# FPGA_Inputs.net
KiCad netlist of a schematic drawn in Altium Designer
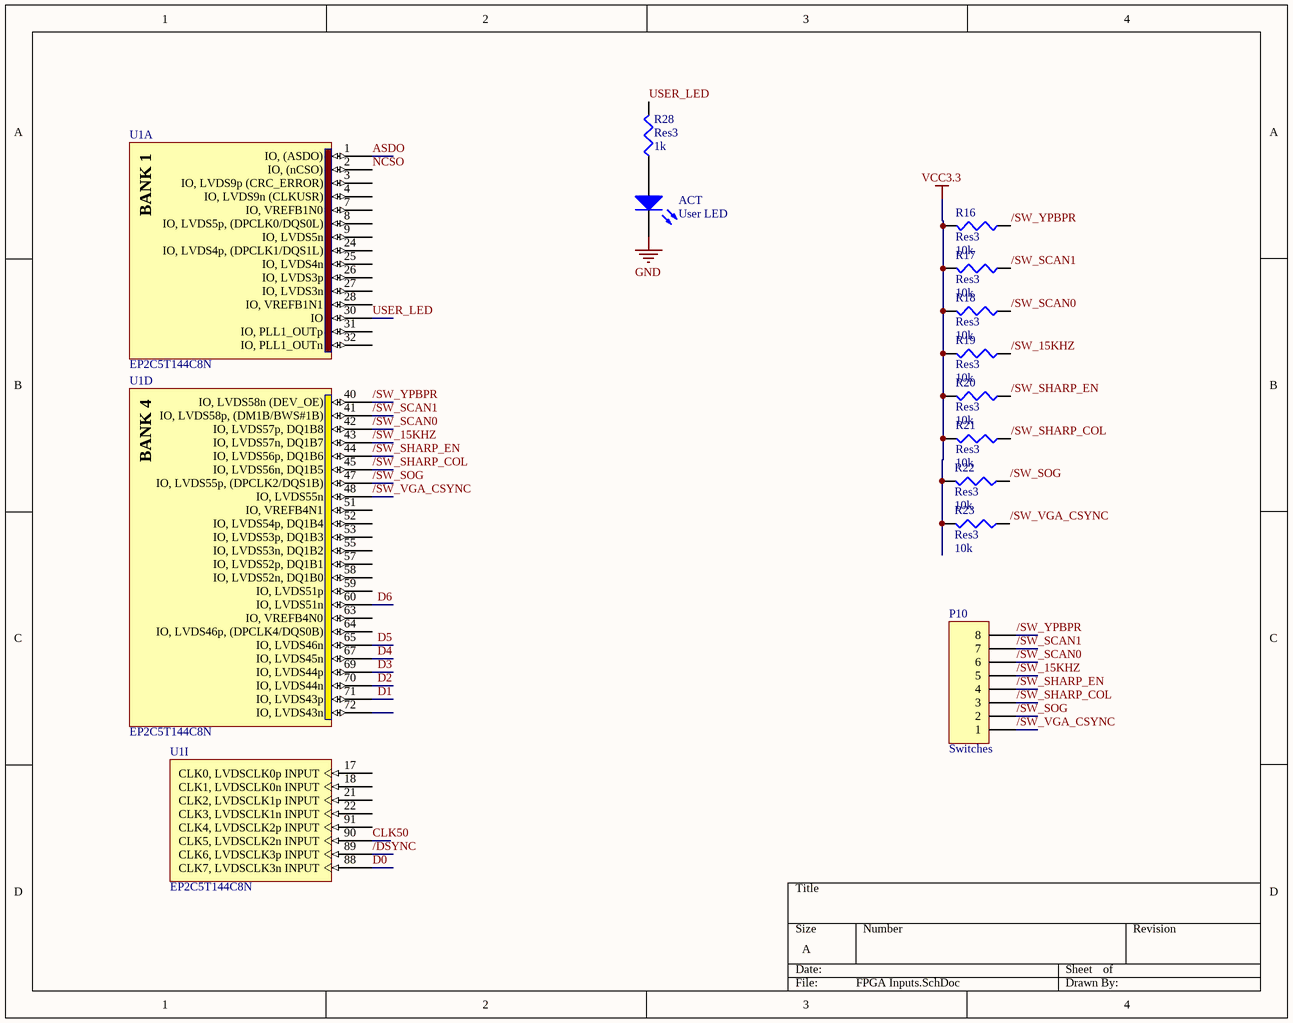
[diagram p0: FPGA Inputs.SchDoc]

(export (version "E")
  (design (tool "Eeschema 10.0.6"))
  (components
    (comp (ref "ACT")
      (value "User LED")
      (footprint "1608[0603]")
      (description "Typical RED, GREEN, YELLOW, AMBER GaAs LED")
      (fields (field (name "PUBLISHER") "Altium Limited"))
      (libsource (lib "Miscellaneous Devices") (part "LED2"))
    )
    (comp (ref "P10")
      (value "Switches")
      (footprint "HDR1X8")
      (description "Header, 8-Pin")
      (fields (field (name "PUBLISHER") "Altium Limited"))
      (libsource (lib "Miscellaneous Connectors") (part "Header 8"))
    )
    (comp (ref "R16")
      (value "Res3")
      (footprint "J1-0603")
      (description "Resistor")
      (fields (field (name "ALTIUM_VALUE") "10k") (field (name "PUBLISHER") "Altium Limited"))
      (libsource (lib "Miscellaneous Devices") (part "Res3"))
    )
    (comp (ref "R17")
      (value "Res3")
      (footprint "J1-0603")
      (description "Resistor")
      (fields (field (name "ALTIUM_VALUE") "10k") (field (name "PUBLISHER") "Altium Limited"))
      (libsource (lib "Miscellaneous Devices") (part "Res3"))
    )
    (comp (ref "R18")
      (value "Res3")
      (footprint "J1-0603")
      (description "Resistor")
      (fields (field (name "ALTIUM_VALUE") "10k") (field (name "PUBLISHER") "Altium Limited"))
      (libsource (lib "Miscellaneous Devices") (part "Res3"))
    )
    (comp (ref "R19")
      (value "Res3")
      (footprint "J1-0603")
      (description "Resistor")
      (fields (field (name "ALTIUM_VALUE") "10k") (field (name "PUBLISHER") "Altium Limited"))
      (libsource (lib "Miscellaneous Devices") (part "Res3"))
    )
    (comp (ref "R20")
      (value "Res3")
      (footprint "J1-0603")
      (description "Resistor")
      (fields (field (name "ALTIUM_VALUE") "10k") (field (name "PUBLISHER") "Altium Limited"))
      (libsource (lib "Miscellaneous Devices") (part "Res3"))
    )
    (comp (ref "R21")
      (value "Res3")
      (footprint "J1-0603")
      (description "Resistor")
      (fields (field (name "ALTIUM_VALUE") "10k") (field (name "PUBLISHER") "Altium Limited"))
      (libsource (lib "Miscellaneous Devices") (part "Res3"))
    )
    (comp (ref "R22")
      (value "Res3")
      (footprint "J1-0603")
      (description "Resistor")
      (fields (field (name "ALTIUM_VALUE") "10k") (field (name "PUBLISHER") "Altium Limited"))
      (libsource (lib "Miscellaneous Devices") (part "Res3"))
    )
    (comp (ref "R23")
      (value "Res3")
      (footprint "J1-0603")
      (description "Resistor")
      (fields (field (name "ALTIUM_VALUE") "10k") (field (name "PUBLISHER") "Altium Limited"))
      (libsource (lib "Miscellaneous Devices") (part "Res3"))
    )
    (comp (ref "R28")
      (value "Res3")
      (footprint "J1-0603")
      (description "Resistor")
      (fields (field (name "ALTIUM_VALUE") "1k") (field (name "PUBLISHER") "Altium Limited"))
      (libsource (lib "Miscellaneous Devices") (part "Res3"))
    )
    (comp (ref "U1")
      (value "EP2C5T144C8N")
      (footprint "TQFP144_N")
      (fields (field (name "PUBLISHER") "Altium Limited"))
      (libsource (lib "Altera Cyclone II") (part "EP2C5T144C8N"))
    )
  )
  (nets
    (net (code "1") (name "/ASDO") (class "Default")
      (node (ref "U1") (pin "1") (pinfunction "IO,_(ASDO)_1") (pintype "bidirectional"))
    )
    (net (code "2") (name "/CLK50") (class "Default")
      (node (ref "U1") (pin "90") (pinfunction "CLK5,_LVDSCLK2n_INPUT_90") (pintype "input"))
    )
    (net (code "3") (name "/D0") (class "Default")
      (node (ref "U1") (pin "88") (pinfunction "CLK7,_LVDSCLK3n_INPUT_88") (pintype "input"))
    )
    (net (code "4") (name "/D1") (class "Default")
      (node (ref "U1") (pin "71") (pinfunction "IO,_LVDS43p_71") (pintype "bidirectional"))
    )
    (net (code "5") (name "/D2") (class "Default")
      (node (ref "U1") (pin "70") (pinfunction "IO,_LVDS44n_70") (pintype "bidirectional"))
    )
    (net (code "6") (name "/D3") (class "Default")
      (node (ref "U1") (pin "69") (pinfunction "IO,_LVDS44p_69") (pintype "bidirectional"))
    )
    (net (code "7") (name "/D4") (class "Default")
      (node (ref "U1") (pin "67") (pinfunction "IO,_LVDS45n_67") (pintype "bidirectional"))
    )
    (net (code "8") (name "/D5") (class "Default")
      (node (ref "U1") (pin "65") (pinfunction "IO,_LVDS46n_65") (pintype "bidirectional"))
    )
    (net (code "9") (name "/D6") (class "Default")
      (node (ref "U1") (pin "60") (pinfunction "IO,_LVDS51n_60") (pintype "bidirectional"))
    )
    (net (code "10") (name "/NCSO") (class "Default")
      (node (ref "U1") (pin "2") (pinfunction "IO,_(nCSO)_2") (pintype "bidirectional"))
    )
    (net (code "11") (name "/USER_LED") (class "Default")
      (node (ref "R28") (pin "2") (pinfunction "2_2") (pintype "passive"))
      (node (ref "U1") (pin "30") (pinfunction "IO_30") (pintype "bidirectional"))
    )
    (net (code "12") (name "/{slash}DSYNC") (class "Default")
      (node (ref "U1") (pin "89") (pinfunction "CLK6,_LVDSCLK3p_INPUT_89") (pintype "input"))
    )
    (net (code "13") (name "/{slash}SW_15KHZ") (class "Default")
      (node (ref "P10") (pin "5") (pinfunction "5_5") (pintype "passive"))
      (node (ref "R19") (pin "1") (pinfunction "1_1") (pintype "passive"))
      (node (ref "U1") (pin "43") (pinfunction "IO,_LVDS57n,_DQ1B7_43") (pintype "bidirectional"))
    )
    (net (code "14") (name "/{slash}SW_SCAN0") (class "Default")
      (node (ref "P10") (pin "6") (pinfunction "6_6") (pintype "passive"))
      (node (ref "R18") (pin "1") (pinfunction "1_1") (pintype "passive"))
      (node (ref "U1") (pin "42") (pinfunction "IO,_LVDS57p,_DQ1B8_42") (pintype "bidirectional"))
    )
    (net (code "15") (name "/{slash}SW_SCAN1") (class "Default")
      (node (ref "P10") (pin "7") (pinfunction "7_7") (pintype "passive"))
      (node (ref "R17") (pin "1") (pinfunction "1_1") (pintype "passive"))
      (node (ref "U1") (pin "41") (pinfunction "IO,_LVDS58p,_(DM1B/BWS#1B)_41") (pintype "bidirectional"))
    )
    (net (code "16") (name "/{slash}SW_SHARP_COL") (class "Default")
      (node (ref "P10") (pin "3") (pinfunction "3_3") (pintype "passive"))
      (node (ref "R21") (pin "1") (pinfunction "1_1") (pintype "passive"))
      (node (ref "U1") (pin "45") (pinfunction "IO,_LVDS56n,_DQ1B5_45") (pintype "bidirectional"))
    )
    (net (code "17") (name "/{slash}SW_SHARP_EN") (class "Default")
      (node (ref "P10") (pin "4") (pinfunction "4_4") (pintype "passive"))
      (node (ref "R20") (pin "1") (pinfunction "1_1") (pintype "passive"))
      (node (ref "U1") (pin "44") (pinfunction "IO,_LVDS56p,_DQ1B6_44") (pintype "bidirectional"))
    )
    (net (code "18") (name "/{slash}SW_SOG") (class "Default")
      (node (ref "P10") (pin "2") (pinfunction "2_2") (pintype "passive"))
      (node (ref "R22") (pin "1") (pinfunction "1_1") (pintype "passive"))
      (node (ref "U1") (pin "47") (pinfunction "IO,_LVDS55p,_(DPCLK2/DQS1B)_47") (pintype "bidirectional"))
    )
    (net (code "19") (name "/{slash}SW_VGA_CSYNC") (class "Default")
      (node (ref "P10") (pin "1") (pinfunction "1_1") (pintype "passive"))
      (node (ref "R23") (pin "1") (pinfunction "1_1") (pintype "passive"))
      (node (ref "U1") (pin "48") (pinfunction "IO,_LVDS55n_48") (pintype "bidirectional"))
    )
    (net (code "20") (name "/{slash}SW_YPBPR") (class "Default")
      (node (ref "P10") (pin "8") (pinfunction "8_8") (pintype "passive"))
      (node (ref "R16") (pin "1") (pinfunction "1_1") (pintype "passive"))
      (node (ref "U1") (pin "40") (pinfunction "IO,_LVDS58n_(DEV_OE)_40") (pintype "bidirectional"))
    )
    (net (code "21") (name "GND") (class "Default")
      (node (ref "ACT") (pin "2") (pinfunction "K_2") (pintype "passive"))
    )
    (net (code "22") (name "Net-(ACT-A)") (class "Default")
      (node (ref "ACT") (pin "1") (pinfunction "A_1") (pintype "passive"))
      (node (ref "R28") (pin "1") (pinfunction "1_1") (pintype "passive"))
    )
    (net (code "23") (name "VCC3.3") (class "Default")
      (node (ref "R16") (pin "2") (pinfunction "2_2") (pintype "passive"))
      (node (ref "R17") (pin "2") (pinfunction "2_2") (pintype "passive"))
      (node (ref "R18") (pin "2") (pinfunction "2_2") (pintype "passive"))
      (node (ref "R19") (pin "2") (pinfunction "2_2") (pintype "passive"))
      (node (ref "R20") (pin "2") (pinfunction "2_2") (pintype "passive"))
      (node (ref "R21") (pin "2") (pinfunction "2_2") (pintype "passive"))
      (node (ref "R22") (pin "2") (pinfunction "2_2") (pintype "passive"))
      (node (ref "R23") (pin "2") (pinfunction "2_2") (pintype "passive"))
    )
    (net (code "24") (name "unconnected-(U1A-IO,_LVDS3n-Pad27)") (class "Default")
      (node (ref "U1") (pin "27") (pinfunction "IO,_LVDS3n_27") (pintype "bidirectional"))
    )
    (net (code "25") (name "unconnected-(U1A-IO,_LVDS3p-Pad26)") (class "Default")
      (node (ref "U1") (pin "26") (pinfunction "IO,_LVDS3p_26") (pintype "bidirectional"))
    )
    (net (code "26") (name "unconnected-(U1A-IO,_LVDS4n-Pad25)") (class "Default")
      (node (ref "U1") (pin "25") (pinfunction "IO,_LVDS4n_25") (pintype "bidirectional"))
    )
    (net (code "27") (name "unconnected-(U1A-IO,_LVDS4p,_(DPCLK1{slash}DQS1L)-Pad24)") (class "Default")
      (node (ref "U1") (pin "24") (pinfunction "IO,_LVDS4p,_(DPCLK1/DQS1L)_24") (pintype "bidirectional"))
    )
    (net (code "28") (name "unconnected-(U1A-IO,_LVDS5n-Pad9)") (class "Default")
      (node (ref "U1") (pin "9") (pinfunction "IO,_LVDS5n_9") (pintype "bidirectional"))
    )
    (net (code "29") (name "unconnected-(U1A-IO,_LVDS5p,_(DPCLK0{slash}DQS0L)-Pad8)") (class "Default")
      (node (ref "U1") (pin "8") (pinfunction "IO,_LVDS5p,_(DPCLK0/DQS0L)_8") (pintype "bidirectional"))
    )
    (net (code "30") (name "unconnected-(U1A-IO,_LVDS9n_(CLKUSR)-Pad4)") (class "Default")
      (node (ref "U1") (pin "4") (pinfunction "IO,_LVDS9n_(CLKUSR)_4") (pintype "bidirectional"))
    )
    (net (code "31") (name "unconnected-(U1A-IO,_LVDS9p_(CRC_ERROR)-Pad3)") (class "Default")
      (node (ref "U1") (pin "3") (pinfunction "IO,_LVDS9p_(CRC_ERROR)_3") (pintype "bidirectional"))
    )
    (net (code "32") (name "unconnected-(U1A-IO,_PLL1_OUTn-Pad32)") (class "Default")
      (node (ref "U1") (pin "32") (pinfunction "IO,_PLL1_OUTn_32") (pintype "bidirectional"))
    )
    (net (code "33") (name "unconnected-(U1A-IO,_PLL1_OUTp-Pad31)") (class "Default")
      (node (ref "U1") (pin "31") (pinfunction "IO,_PLL1_OUTp_31") (pintype "bidirectional"))
    )
    (net (code "34") (name "unconnected-(U1A-IO,_VREFB1N0-Pad7)") (class "Default")
      (node (ref "U1") (pin "7") (pinfunction "IO,_VREFB1N0_7") (pintype "bidirectional"))
    )
    (net (code "35") (name "unconnected-(U1A-IO,_VREFB1N1-Pad28)") (class "Default")
      (node (ref "U1") (pin "28") (pinfunction "IO,_VREFB1N1_28") (pintype "bidirectional"))
    )
    (net (code "36") (name "unconnected-(U1D-IO,_LVDS43n-Pad72)") (class "Default")
      (node (ref "U1") (pin "72") (pinfunction "IO,_LVDS43n_72") (pintype "bidirectional"))
    )
    (net (code "37") (name "unconnected-(U1D-IO,_LVDS46p,_(DPCLK4{slash}DQS0B)-Pad64)") (class "Default")
      (node (ref "U1") (pin "64") (pinfunction "IO,_LVDS46p,_(DPCLK4/DQS0B)_64") (pintype "bidirectional"))
    )
    (net (code "38") (name "unconnected-(U1D-IO,_LVDS51p-Pad59)") (class "Default")
      (node (ref "U1") (pin "59") (pinfunction "IO,_LVDS51p_59") (pintype "bidirectional"))
    )
    (net (code "39") (name "unconnected-(U1D-IO,_LVDS52n,_DQ1B0-Pad58)") (class "Default")
      (node (ref "U1") (pin "58") (pinfunction "IO,_LVDS52n,_DQ1B0_58") (pintype "bidirectional"))
    )
    (net (code "40") (name "unconnected-(U1D-IO,_LVDS52p,_DQ1B1-Pad57)") (class "Default")
      (node (ref "U1") (pin "57") (pinfunction "IO,_LVDS52p,_DQ1B1_57") (pintype "bidirectional"))
    )
    (net (code "41") (name "unconnected-(U1D-IO,_LVDS53n,_DQ1B2-Pad55)") (class "Default")
      (node (ref "U1") (pin "55") (pinfunction "IO,_LVDS53n,_DQ1B2_55") (pintype "bidirectional"))
    )
    (net (code "42") (name "unconnected-(U1D-IO,_LVDS53p,_DQ1B3-Pad53)") (class "Default")
      (node (ref "U1") (pin "53") (pinfunction "IO,_LVDS53p,_DQ1B3_53") (pintype "bidirectional"))
    )
    (net (code "43") (name "unconnected-(U1D-IO,_LVDS54p,_DQ1B4-Pad52)") (class "Default")
      (node (ref "U1") (pin "52") (pinfunction "IO,_LVDS54p,_DQ1B4_52") (pintype "bidirectional"))
    )
    (net (code "44") (name "unconnected-(U1D-IO,_VREFB4N0-Pad63)") (class "Default")
      (node (ref "U1") (pin "63") (pinfunction "IO,_VREFB4N0_63") (pintype "bidirectional"))
    )
    (net (code "45") (name "unconnected-(U1D-IO,_VREFB4N1-Pad51)") (class "Default")
      (node (ref "U1") (pin "51") (pinfunction "IO,_VREFB4N1_51") (pintype "bidirectional"))
    )
    (net (code "46") (name "unconnected-(U1I-CLK0,_LVDSCLK0p_INPUT-Pad17)") (class "Default")
      (node (ref "U1") (pin "17") (pinfunction "CLK0,_LVDSCLK0p_INPUT_17") (pintype "input"))
    )
    (net (code "47") (name "unconnected-(U1I-CLK1,_LVDSCLK0n_INPUT-Pad18)") (class "Default")
      (node (ref "U1") (pin "18") (pinfunction "CLK1,_LVDSCLK0n_INPUT_18") (pintype "input"))
    )
    (net (code "48") (name "unconnected-(U1I-CLK2,_LVDSCLK1p_INPUT-Pad21)") (class "Default")
      (node (ref "U1") (pin "21") (pinfunction "CLK2,_LVDSCLK1p_INPUT_21") (pintype "input"))
    )
    (net (code "49") (name "unconnected-(U1I-CLK3,_LVDSCLK1n_INPUT-Pad22)") (class "Default")
      (node (ref "U1") (pin "22") (pinfunction "CLK3,_LVDSCLK1n_INPUT_22") (pintype "input"))
    )
    (net (code "50") (name "unconnected-(U1I-CLK4,_LVDSCLK2p_INPUT-Pad91)") (class "Default")
      (node (ref "U1") (pin "91") (pinfunction "CLK4,_LVDSCLK2p_INPUT_91") (pintype "input"))
    )
  )
)
